# RS232.net
KiCad netlist of a schematic drawn in Altium Designer
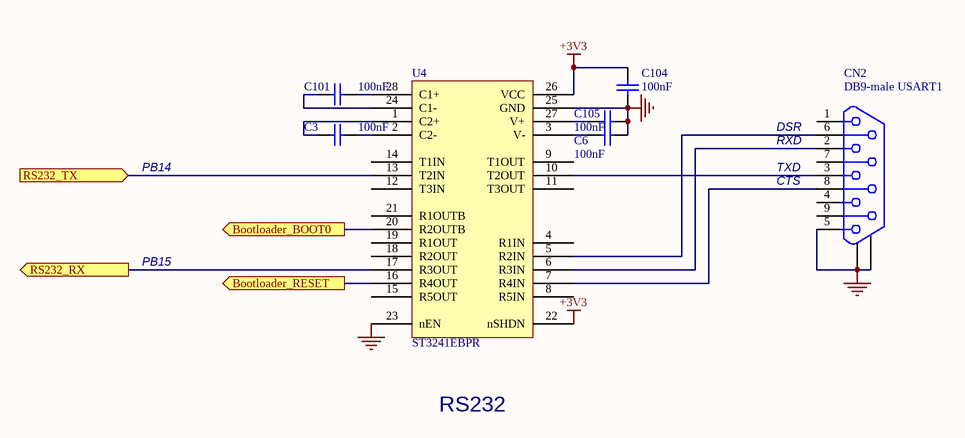
[diagram p0: RS232.SchDoc]

(export (version "E")
  (design (tool "Eeschema 10.0.6"))
  (components
    (comp (ref "C3")
      (value "100nF")
      (footprint "0603C")
      (description "Capacitor")
      (fields (field (name "PUBLISHER") "Altium Limited"))
      (libsource (lib "Miscellaneous Devices") (part "Cap"))
    )
    (comp (ref "C6")
      (value "100nF")
      (footprint "0603C")
      (description "Capacitor")
      (fields (field (name "PUBLISHER") "Altium Limited"))
      (libsource (lib "Miscellaneous Devices") (part "Cap"))
    )
    (comp (ref "C101")
      (value "100nF")
      (footprint "0603C")
      (description "Capacitor")
      (fields (field (name "PUBLISHER") "Altium Limited"))
      (libsource (lib "Miscellaneous Devices") (part "Cap"))
    )
    (comp (ref "C104")
      (value "100nF")
      (footprint "0603C")
      (description "Capacitor")
      (fields (field (name "PUBLISHER") "Altium Limited"))
      (libsource (lib "Miscellaneous Devices") (part "Cap"))
    )
    (comp (ref "C105")
      (value "100nF")
      (footprint "0603C")
      (description "Capacitor")
      (fields (field (name "PUBLISHER") "Altium Limited"))
      (libsource (lib "Miscellaneous Devices") (part "Cap"))
    )
    (comp (ref "CN2")
      (value "DB9-male USART1")
      (footprint "DB9/M")
      (libsource (lib "mb1045") (part "DB9-USART"))
    )
    (comp (ref "U4")
      (value "ST3241EBPR")
      (footprint "SSOP28_0R65_10R2X7R8")
      (libsource (lib "*") (part "ST3241"))
    )
  )
  (nets
    (net (code "1") (name "+3V3") (class "Default")
      (node (ref "C104") (pin "1") (pinfunction "1_1") (pintype "passive"))
      (node (ref "U4") (pin "22") (pinfunction "nSHDN_22") (pintype "passive"))
      (node (ref "U4") (pin "26") (pinfunction "VCC_26") (pintype "passive"))
    )
    (net (code "2") (name "/Bootloader_BOOT0") (class "Default")
      (node (ref "U4") (pin "20") (pinfunction "R2OUTB_20") (pintype "passive"))
    )
    (net (code "3") (name "/Bootloader_RESET") (class "Default")
      (node (ref "U4") (pin "16") (pinfunction "R4OUT_16") (pintype "passive"))
    )
    (net (code "4") (name "/RS232_RX") (class "Default")
      (node (ref "U4") (pin "17") (pinfunction "R3OUT_17") (pintype "passive"))
    )
    (net (code "5") (name "/RS232_TX") (class "Default")
      (node (ref "U4") (pin "13") (pinfunction "T2IN_13") (pintype "passive"))
    )
    (net (code "6") (name "GND") (class "Default")
      (node (ref "C104") (pin "2") (pinfunction "2_2") (pintype "passive"))
      (node (ref "C105") (pin "1") (pinfunction "1_1") (pintype "passive"))
      (node (ref "C6") (pin "1") (pinfunction "1_1") (pintype "passive"))
      (node (ref "CN2") (pin "10") (pinfunction "10_10") (pintype "passive"))
      (node (ref "CN2") (pin "11") (pinfunction "11_11") (pintype "passive"))
      (node (ref "CN2") (pin "5") (pinfunction "5_5") (pintype "passive"))
      (node (ref "U4") (pin "23") (pinfunction "nEN_23") (pintype "passive"))
      (node (ref "U4") (pin "25") (pinfunction "GND_25") (pintype "passive"))
    )
    (net (code "7") (name "Net-(U4-C1+)") (class "Default")
      (node (ref "C101") (pin "2") (pinfunction "2_2") (pintype "passive"))
      (node (ref "U4") (pin "28") (pinfunction "C1+_28") (pintype "passive"))
    )
    (net (code "8") (name "Net-(U4-C1-)") (class "Default")
      (node (ref "C101") (pin "1") (pinfunction "1_1") (pintype "passive"))
      (node (ref "U4") (pin "24") (pinfunction "C1-_24") (pintype "passive"))
    )
    (net (code "9") (name "Net-(U4-C2+)") (class "Default")
      (node (ref "C3") (pin "1") (pinfunction "1_1") (pintype "passive"))
      (node (ref "U4") (pin "1") (pinfunction "C2+_1") (pintype "passive"))
    )
    (net (code "10") (name "Net-(U4-C2-)") (class "Default")
      (node (ref "C3") (pin "2") (pinfunction "2_2") (pintype "passive"))
      (node (ref "U4") (pin "2") (pinfunction "C2-_2") (pintype "passive"))
    )
    (net (code "11") (name "Net-(U4-R2IN)") (class "Default")
      (node (ref "CN2") (pin "6") (pinfunction "6_6") (pintype "passive"))
      (node (ref "U4") (pin "5") (pinfunction "R2IN_5") (pintype "passive"))
    )
    (net (code "12") (name "Net-(U4-R3IN)") (class "Default")
      (node (ref "CN2") (pin "2") (pinfunction "2_2") (pintype "passive"))
      (node (ref "U4") (pin "6") (pinfunction "R3IN_6") (pintype "passive"))
    )
    (net (code "13") (name "Net-(U4-R4IN)") (class "Default")
      (node (ref "CN2") (pin "8") (pinfunction "8_8") (pintype "passive"))
      (node (ref "U4") (pin "7") (pinfunction "R4IN_7") (pintype "passive"))
    )
    (net (code "14") (name "Net-(U4-T2OUT)") (class "Default")
      (node (ref "CN2") (pin "3") (pinfunction "3_3") (pintype "passive"))
      (node (ref "U4") (pin "10") (pinfunction "T2OUT_10") (pintype "passive"))
    )
    (net (code "15") (name "Net-(U4-V+)") (class "Default")
      (node (ref "C105") (pin "2") (pinfunction "2_2") (pintype "passive"))
      (node (ref "U4") (pin "27") (pinfunction "V+_27") (pintype "passive"))
    )
    (net (code "16") (name "Net-(U4-V-)") (class "Default")
      (node (ref "C6") (pin "2") (pinfunction "2_2") (pintype "passive"))
      (node (ref "U4") (pin "3") (pinfunction "V-_3") (pintype "passive"))
    )
    (net (code "17") (name "unconnected-(CN2-Pad1)") (class "Default")
      (node (ref "CN2") (pin "1") (pinfunction "1_1") (pintype "passive"))
    )
    (net (code "18") (name "unconnected-(CN2-Pad4)") (class "Default")
      (node (ref "CN2") (pin "4") (pinfunction "4_4") (pintype "passive"))
    )
    (net (code "19") (name "unconnected-(CN2-Pad7)") (class "Default")
      (node (ref "CN2") (pin "7") (pinfunction "7_7") (pintype "passive"))
    )
    (net (code "20") (name "unconnected-(CN2-Pad9)") (class "Default")
      (node (ref "CN2") (pin "9") (pinfunction "9_9") (pintype "passive"))
    )
    (net (code "21") (name "unconnected-(U4-R1IN-Pad4)") (class "Default")
      (node (ref "U4") (pin "4") (pinfunction "R1IN_4") (pintype "passive"))
    )
    (net (code "22") (name "unconnected-(U4-R1OUT-Pad19)") (class "Default")
      (node (ref "U4") (pin "19") (pinfunction "R1OUT_19") (pintype "passive"))
    )
    (net (code "23") (name "unconnected-(U4-R1OUTB-Pad21)") (class "Default")
      (node (ref "U4") (pin "21") (pinfunction "R1OUTB_21") (pintype "passive"))
    )
    (net (code "24") (name "unconnected-(U4-R2OUT-Pad18)") (class "Default")
      (node (ref "U4") (pin "18") (pinfunction "R2OUT_18") (pintype "passive"))
    )
    (net (code "25") (name "unconnected-(U4-R5IN-Pad8)") (class "Default")
      (node (ref "U4") (pin "8") (pinfunction "R5IN_8") (pintype "passive"))
    )
    (net (code "26") (name "unconnected-(U4-R5OUT-Pad15)") (class "Default")
      (node (ref "U4") (pin "15") (pinfunction "R5OUT_15") (pintype "passive"))
    )
    (net (code "27") (name "unconnected-(U4-T1IN-Pad14)") (class "Default")
      (node (ref "U4") (pin "14") (pinfunction "T1IN_14") (pintype "passive"))
    )
    (net (code "28") (name "unconnected-(U4-T1OUT-Pad9)") (class "Default")
      (node (ref "U4") (pin "9") (pinfunction "T1OUT_9") (pintype "passive"))
    )
    (net (code "29") (name "unconnected-(U4-T3IN-Pad12)") (class "Default")
      (node (ref "U4") (pin "12") (pinfunction "T3IN_12") (pintype "passive"))
    )
    (net (code "30") (name "unconnected-(U4-T3OUT-Pad11)") (class "Default")
      (node (ref "U4") (pin "11") (pinfunction "T3OUT_11") (pintype "passive"))
    )
  )
)
